# BBB_Headers.net
KiCad netlist of a schematic drawn in Altium Designer
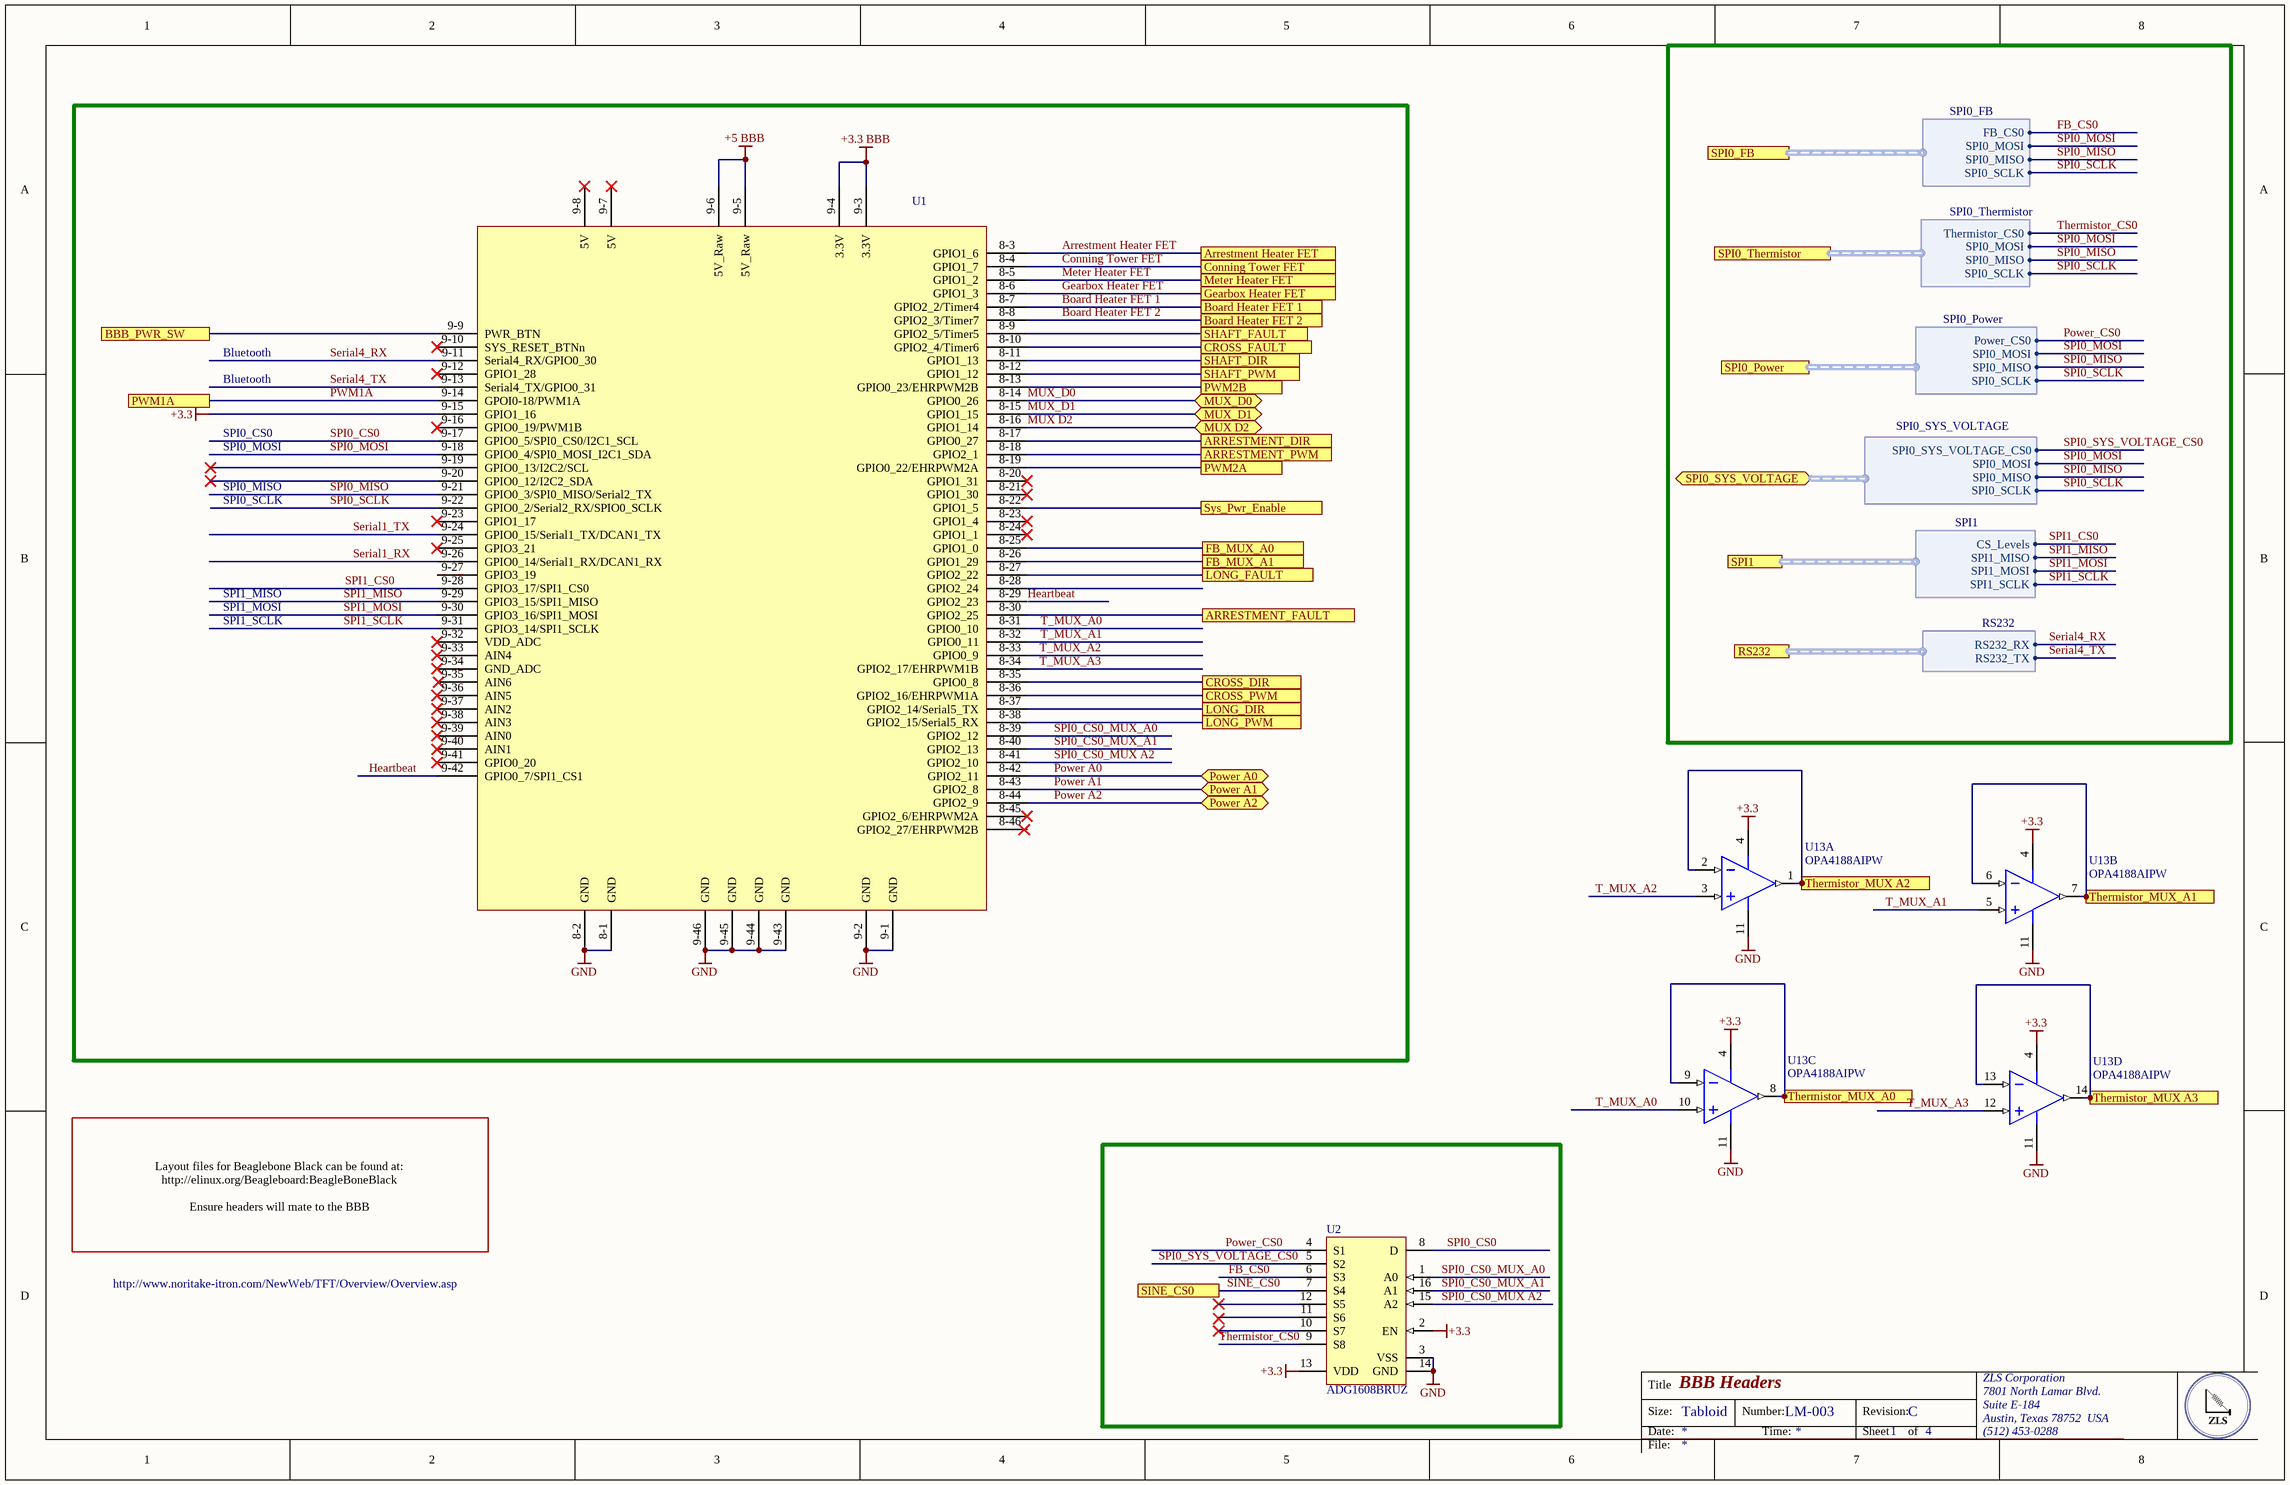
[diagram p0: BBB Headers.SchDoc]

(export (version "E")
  (design (tool "Eeschema 10.0.6"))
  (components
    (comp (ref "U1")
      (value "BBB Header x 2")
      (footprint "Beaglebone Black Thru")
      (description "Beaglebone Black Header")
      (fields
        (field (name "MANUFACTURER") "Samtec Inc.")
        (field (name "MANUFACTURER PART NUMBER") "SSW-123-03-G-D")
      )
      (libsource (lib "ZLS_Schematic_lib") (part "Beaglebone_Black"))
    )
    (comp (ref "U2")
      (value "ADG1608BRUZ")
      (footprint "ADI-RU-16_M")
      (description "4.5 Ohm Ron, 8-Channel +/-5 V,+12 V, +5 V and +3.3 V Multiplexer, 16-pin SOP (RU-16), Tube")
      (fields (field (name "MANUFACTURER") "Analog Devices Inc.") (field (name "BASE PART NUMBER") "ADG1608"))
      (libsource (lib "Altium Content Vault") (part "CMP-0793-00136-1"))
    )
    (comp (ref "U13")
      (value "OPA4188AIPW")
      (footprint "PW0014A_L")
      (fields (field (name "MANUFACTURER") "Texas Instruments"))
      (libsource (lib "Altium Content Vault") (part "TI-OPA4188-PW14"))
    )
  )
  (nets
    (net (code "7") (name "+3.3") (class "Default")
      (node (ref "U1") (pin "9-15") (pinfunction "GPIO1_16_9-15") (pintype "passive"))
      (node (ref "U13") (pin "4") (pinfunction "V+_4") (pintype "power_in"))
      (node (ref "U2") (pin "13") (pinfunction "VDD_13") (pintype "power_in"))
      (node (ref "U2") (pin "2") (pinfunction "EN_2") (pintype "input"))
    )
    (net (code "8") (name "+3.3 BBB") (class "Default")
      (node (ref "U1") (pin "9-3") (pinfunction "3.3V_9-3") (pintype "passive"))
      (node (ref "U1") (pin "9-4") (pinfunction "3.3V_9-4") (pintype "passive"))
    )
    (net (code "9") (name "+5 BBB") (class "Default")
      (node (ref "U1") (pin "9-5") (pinfunction "5V_Raw_9-5") (pintype "passive"))
      (node (ref "U1") (pin "9-6") (pinfunction "5V_Raw_9-6") (pintype "passive"))
    )
    (net (code "10") (name "/ARRESTMENT_DIR") (class "Default")
      (node (ref "U1") (pin "8-17") (pinfunction "GPIO0_27_8-17") (pintype "passive"))
    )
    (net (code "11") (name "/ARRESTMENT_FAULT") (class "Default")
      (node (ref "U1") (pin "8-30") (pinfunction "GPIO2_25_8-30") (pintype "passive"))
    )
    (net (code "12") (name "/ARRESTMENT_PWM") (class "Default")
      (node (ref "U1") (pin "8-18") (pinfunction "GPIO2_1_8-18") (pintype "passive"))
    )
    (net (code "13") (name "/Arrestment Heater FET") (class "Default")
      (node (ref "U1") (pin "8-3") (pinfunction "GPIO1_6_8-3") (pintype "passive"))
    )
    (net (code "14") (name "/BBB_PWR_SW") (class "Default")
      (node (ref "U1") (pin "9-9") (pinfunction "PWR_BTN_9-9") (pintype "passive"))
    )
    (net (code "15") (name "/Board Heater FET 1") (class "Default")
      (node (ref "U1") (pin "8-7") (pinfunction "GPIO2_2/Timer4_8-7") (pintype "passive"))
    )
    (net (code "16") (name "/Board Heater FET 2") (class "Default")
      (node (ref "U1") (pin "8-8") (pinfunction "GPIO2_3/Timer7_8-8") (pintype "passive"))
    )
    (net (code "17") (name "/CROSS_DIR") (class "Default")
      (node (ref "U1") (pin "8-35") (pinfunction "GPIO0_8_8-35") (pintype "passive"))
    )
    (net (code "18") (name "/CROSS_FAULT") (class "Default")
      (node (ref "U1") (pin "8-10") (pinfunction "GPIO2_4/Timer6_8-10") (pintype "passive"))
    )
    (net (code "19") (name "/CROSS_PWM") (class "Default")
      (node (ref "U1") (pin "8-36") (pinfunction "GPIO2_16/EHRPWM1A_8-36") (pintype "passive"))
    )
    (net (code "20") (name "/Conning Tower FET") (class "Default")
      (node (ref "U1") (pin "8-4") (pinfunction "GPIO1_7_8-4") (pintype "passive"))
    )
    (net (code "21") (name "/FB_CS0") (class "Default")
      (node (ref "U2") (pin "6") (pinfunction "S3_6") (pintype "passive"))
    )
    (net (code "22") (name "/FB_MUX_A0") (class "Default")
      (node (ref "U1") (pin "8-25") (pinfunction "GPIO1_0_8-25") (pintype "passive"))
    )
    (net (code "23") (name "/FB_MUX_A1") (class "Default")
      (node (ref "U1") (pin "8-26") (pinfunction "GPIO1_29_8-26") (pintype "passive"))
    )
    (net (code "24") (name "/Gearbox Heater FET") (class "Default")
      (node (ref "U1") (pin "8-6") (pinfunction "GPIO1_3_8-6") (pintype "passive"))
    )
    (net (code "25") (name "/Heartbeat") (class "Default")
      (node (ref "U1") (pin "8-29") (pinfunction "GPIO2_23_8-29") (pintype "passive"))
      (node (ref "U1") (pin "9-42") (pinfunction "GPIO0_7/SPI1_CS1_9-42") (pintype "passive"))
    )
    (net (code "26") (name "/LONG_DIR") (class "Default")
      (node (ref "U1") (pin "8-37") (pinfunction "GPIO2_14/Serial5_TX_8-37") (pintype "passive"))
    )
    (net (code "27") (name "/LONG_FAULT") (class "Default")
      (node (ref "U1") (pin "8-27") (pinfunction "GPIO2_22_8-27") (pintype "passive"))
    )
    (net (code "28") (name "/LONG_PWM") (class "Default")
      (node (ref "U1") (pin "8-38") (pinfunction "GPIO2_15/Serial5_RX_8-38") (pintype "passive"))
    )
    (net (code "29") (name "/MUX D2") (class "Default")
      (node (ref "U1") (pin "8-16") (pinfunction "GPIO1_14_8-16") (pintype "passive"))
    )
    (net (code "30") (name "/MUX_D0") (class "Default")
      (node (ref "U1") (pin "8-14") (pinfunction "GPIO0_26_8-14") (pintype "passive"))
    )
    (net (code "31") (name "/MUX_D1") (class "Default")
      (node (ref "U1") (pin "8-15") (pinfunction "GPIO1_15_8-15") (pintype "passive"))
    )
    (net (code "32") (name "/Meter Heater FET") (class "Default")
      (node (ref "U1") (pin "8-5") (pinfunction "GPIO1_2_8-5") (pintype "passive"))
    )
    (net (code "33") (name "/PWM1A") (class "Default")
      (node (ref "U1") (pin "9-14") (pinfunction "GPOI0-18/PWM1A_9-14") (pintype "passive"))
    )
    (net (code "34") (name "/PWM2A") (class "Default")
      (node (ref "U1") (pin "8-19") (pinfunction "GPIO0_22/EHRPWM2A_8-19") (pintype "passive"))
    )
    (net (code "35") (name "/PWM2B") (class "Default")
      (node (ref "U1") (pin "8-13") (pinfunction "GPIO0_23/EHRPWM2B_8-13") (pintype "passive"))
    )
    (net (code "36") (name "/Power A0") (class "Default")
      (node (ref "U1") (pin "8-42") (pinfunction "GPIO2_11_8-42") (pintype "passive"))
    )
    (net (code "37") (name "/Power A1") (class "Default")
      (node (ref "U1") (pin "8-43") (pinfunction "GPIO2_8_8-43") (pintype "passive"))
    )
    (net (code "38") (name "/Power A2") (class "Default")
      (node (ref "U1") (pin "8-44") (pinfunction "GPIO2_9_8-44") (pintype "passive"))
    )
    (net (code "39") (name "/Power_CS0") (class "Default")
      (node (ref "U2") (pin "4") (pinfunction "S1_4") (pintype "passive"))
    )
    (net (code "40") (name "/SHAFT_DIR") (class "Default")
      (node (ref "U1") (pin "8-11") (pinfunction "GPIO1_13_8-11") (pintype "passive"))
    )
    (net (code "41") (name "/SHAFT_FAULT") (class "Default")
      (node (ref "U1") (pin "8-9") (pinfunction "GPIO2_5/Timer5_8-9") (pintype "passive"))
    )
    (net (code "42") (name "/SHAFT_PWM") (class "Default")
      (node (ref "U1") (pin "8-12") (pinfunction "GPIO1_12_8-12") (pintype "passive"))
    )
    (net (code "43") (name "/SINE_CS0") (class "Default")
      (node (ref "U2") (pin "7") (pinfunction "S4_7") (pintype "passive"))
    )
    (net (code "44") (name "/SPI0_CS0") (class "Default")
      (node (ref "U1") (pin "9-17") (pinfunction "GPIO0_5/SPI0_CS0/I2C1_SCL_9-17") (pintype "passive"))
      (node (ref "U2") (pin "8") (pinfunction "D_8") (pintype "passive"))
    )
    (net (code "45") (name "/SPI0_CS0_MUX A2") (class "Default")
      (node (ref "U1") (pin "8-41") (pinfunction "GPIO2_10_8-41") (pintype "passive"))
      (node (ref "U2") (pin "15") (pinfunction "A2_15") (pintype "input"))
    )
    (net (code "46") (name "/SPI0_CS0_MUX_A0") (class "Default")
      (node (ref "U1") (pin "8-39") (pinfunction "GPIO2_12_8-39") (pintype "passive"))
      (node (ref "U2") (pin "1") (pinfunction "A0_1") (pintype "input"))
    )
    (net (code "47") (name "/SPI0_CS0_MUX_A1") (class "Default")
      (node (ref "U1") (pin "8-40") (pinfunction "GPIO2_13_8-40") (pintype "passive"))
      (node (ref "U2") (pin "16") (pinfunction "A1_16") (pintype "input"))
    )
    (net (code "48") (name "/SPI0_MISO") (class "Default")
      (node (ref "U1") (pin "9-21") (pinfunction "GPIO0_3/SPI0_MISO/Serial2_TX_9-21") (pintype "passive"))
    )
    (net (code "49") (name "/SPI0_MOSI") (class "Default")
      (node (ref "U1") (pin "9-18") (pinfunction "GPIO0_4/SPI0_MOSI_I2C1_SDA_9-18") (pintype "passive"))
    )
    (net (code "50") (name "/SPI0_SCLK") (class "Default")
      (node (ref "U1") (pin "9-22") (pinfunction "GPIO0_2/Serial2_RX/SPIO0_SCLK_9-22") (pintype "passive"))
    )
    (net (code "51") (name "/SPI0_SYS_VOLTAGE_CS0") (class "Default")
      (node (ref "U2") (pin "5") (pinfunction "S2_5") (pintype "passive"))
    )
    (net (code "52") (name "/SPI1_CS0") (class "Default")
      (node (ref "U1") (pin "9-28") (pinfunction "GPIO3_17/SPI1_CS0_9-28") (pintype "passive"))
    )
    (net (code "53") (name "/SPI1_MISO") (class "Default")
      (node (ref "U1") (pin "9-29") (pinfunction "GPIO3_15/SPI1_MISO_9-29") (pintype "passive"))
    )
    (net (code "54") (name "/SPI1_MOSI") (class "Default")
      (node (ref "U1") (pin "9-30") (pinfunction "GPIO3_16/SPI1_MOSI_9-30") (pintype "passive"))
    )
    (net (code "55") (name "/SPI1_SCLK") (class "Default")
      (node (ref "U1") (pin "9-31") (pinfunction "GPIO3_14/SPI1_SCLK_9-31") (pintype "passive"))
    )
    (net (code "56") (name "/Serial1_RX") (class "Default")
      (node (ref "U1") (pin "9-26") (pinfunction "GPIO0_14/Serial1_RX/DCAN1_RX_9-26") (pintype "passive"))
    )
    (net (code "57") (name "/Serial1_TX") (class "Default")
      (node (ref "U1") (pin "9-24") (pinfunction "GPIO0_15/Serial1_TX/DCAN1_TX_9-24") (pintype "passive"))
    )
    (net (code "58") (name "/Serial4_RX") (class "Default")
      (node (ref "U1") (pin "9-11") (pinfunction "Serial4_RX/GPIO0_30_9-11") (pintype "passive"))
    )
    (net (code "59") (name "/Serial4_TX") (class "Default")
      (node (ref "U1") (pin "9-13") (pinfunction "Serial4_TX/GPIO0_31_9-13") (pintype "passive"))
    )
    (net (code "60") (name "/Sys_Pwr_Enable") (class "Default")
      (node (ref "U1") (pin "8-22") (pinfunction "GPIO1_5_8-22") (pintype "passive"))
    )
    (net (code "61") (name "/T_MUX_A0") (class "Default")
      (node (ref "U1") (pin "8-31") (pinfunction "GPIO0_10_8-31") (pintype "passive"))
      (node (ref "U13") (pin "10") (pinfunction "IN_C+_10") (pintype "input"))
    )
    (net (code "62") (name "/T_MUX_A1") (class "Default")
      (node (ref "U1") (pin "8-32") (pinfunction "GPIO0_11_8-32") (pintype "passive"))
      (node (ref "U13") (pin "5") (pinfunction "IN_B+_5") (pintype "input"))
    )
    (net (code "63") (name "/T_MUX_A2") (class "Default")
      (node (ref "U1") (pin "8-33") (pinfunction "GPIO0_9_8-33") (pintype "passive"))
      (node (ref "U13") (pin "3") (pinfunction "IN_A+_3") (pintype "input"))
    )
    (net (code "64") (name "/T_MUX_A3") (class "Default")
      (node (ref "U1") (pin "8-34") (pinfunction "GPIO2_17/EHRPWM1B_8-34") (pintype "passive"))
      (node (ref "U13") (pin "12") (pinfunction "IN_D+_12") (pintype "input"))
    )
    (net (code "65") (name "/Thermistor_CS0") (class "Default")
      (node (ref "U2") (pin "9") (pinfunction "S8_9") (pintype "passive"))
    )
    (net (code "66") (name "/Thermistor_MUX A2") (class "Default")
      (node (ref "U13") (pin "1") (pinfunction "OUT_A_1") (pintype "output"))
      (node (ref "U13") (pin "2") (pinfunction "IN_A-_2") (pintype "input"))
    )
    (net (code "67") (name "/Thermistor_MUX A3") (class "Default")
      (node (ref "U13") (pin "13") (pinfunction "IN_D-_13") (pintype "input"))
      (node (ref "U13") (pin "14") (pinfunction "OUT_D_14") (pintype "output"))
    )
    (net (code "68") (name "/Thermistor_MUX_A0") (class "Default")
      (node (ref "U13") (pin "8") (pinfunction "OUT_C_8") (pintype "output"))
      (node (ref "U13") (pin "9") (pinfunction "IN_C-_9") (pintype "input"))
    )
    (net (code "69") (name "/Thermistor_MUX_A1") (class "Default")
      (node (ref "U13") (pin "6") (pinfunction "IN_B-_6") (pintype "input"))
      (node (ref "U13") (pin "7") (pinfunction "OUT_B_7") (pintype "output"))
    )
    (net (code "76") (name "GND") (class "Default")
      (node (ref "U1") (pin "8-1") (pinfunction "GND_8-1") (pintype "passive"))
      (node (ref "U1") (pin "8-2") (pinfunction "GND_8-2") (pintype "passive"))
      (node (ref "U1") (pin "9-1") (pinfunction "GND_9-1") (pintype "passive"))
      (node (ref "U1") (pin "9-2") (pinfunction "GND_9-2") (pintype "passive"))
      (node (ref "U1") (pin "9-43") (pinfunction "GND_9-43") (pintype "passive"))
      (node (ref "U1") (pin "9-44") (pinfunction "GND_9-44") (pintype "passive"))
      (node (ref "U1") (pin "9-45") (pinfunction "GND_9-45") (pintype "passive"))
      (node (ref "U1") (pin "9-46") (pinfunction "GND_9-46") (pintype "passive"))
      (node (ref "U13") (pin "11") (pinfunction "V-_11") (pintype "power_in"))
      (node (ref "U2") (pin "14") (pinfunction "GND_14") (pintype "power_in"))
      (node (ref "U2") (pin "3") (pinfunction "VSS_3") (pintype "power_in"))
    )
    (net (code "77") (name "unconnected-(U1-5V-Pad9-7)") (class "Default")
      (node (ref "U1") (pin "9-7") (pinfunction "5V_9-7") (pintype "passive+no_connect"))
    )
    (net (code "78") (name "unconnected-(U1-5V-Pad9-8)") (class "Default")
      (node (ref "U1") (pin "9-8") (pinfunction "5V_9-8") (pintype "passive+no_connect"))
    )
    (net (code "79") (name "unconnected-(U1-AIN0-Pad9-39)") (class "Default")
      (node (ref "U1") (pin "9-39") (pinfunction "AIN0_9-39") (pintype "passive+no_connect"))
    )
    (net (code "80") (name "unconnected-(U1-AIN1-Pad9-40)") (class "Default")
      (node (ref "U1") (pin "9-40") (pinfunction "AIN1_9-40") (pintype "passive+no_connect"))
    )
    (net (code "81") (name "unconnected-(U1-AIN2-Pad9-37)") (class "Default")
      (node (ref "U1") (pin "9-37") (pinfunction "AIN2_9-37") (pintype "passive+no_connect"))
    )
    (net (code "82") (name "unconnected-(U1-AIN3-Pad9-38)") (class "Default")
      (node (ref "U1") (pin "9-38") (pinfunction "AIN3_9-38") (pintype "passive+no_connect"))
    )
    (net (code "83") (name "unconnected-(U1-AIN4-Pad9-33)") (class "Default")
      (node (ref "U1") (pin "9-33") (pinfunction "AIN4_9-33") (pintype "passive+no_connect"))
    )
    (net (code "84") (name "unconnected-(U1-AIN5-Pad9-36)") (class "Default")
      (node (ref "U1") (pin "9-36") (pinfunction "AIN5_9-36") (pintype "passive+no_connect"))
    )
    (net (code "85") (name "unconnected-(U1-AIN6-Pad9-35)") (class "Default")
      (node (ref "U1") (pin "9-35") (pinfunction "AIN6_9-35") (pintype "passive"))
    )
    (net (code "86") (name "unconnected-(U1-GND_ADC-Pad9-34)") (class "Default")
      (node (ref "U1") (pin "9-34") (pinfunction "GND_ADC_9-34") (pintype "passive+no_connect"))
    )
    (net (code "87") (name "unconnected-(U1-GPIO0_12{slash}I2C2_SDA-Pad9-20)") (class "Default")
      (node (ref "U1") (pin "9-20") (pinfunction "GPIO0_12/I2C2_SDA_9-20") (pintype "passive+no_connect"))
    )
    (net (code "88") (name "unconnected-(U1-GPIO0_13{slash}I2C2{slash}SCL-Pad9-19)") (class "Default")
      (node (ref "U1") (pin "9-19") (pinfunction "GPIO0_13/I2C2/SCL_9-19") (pintype "passive+no_connect"))
    )
    (net (code "89") (name "unconnected-(U1-GPIO0_19{slash}PWM1B-Pad9-16)") (class "Default")
      (node (ref "U1") (pin "9-16") (pinfunction "GPIO0_19/PWM1B_9-16") (pintype "passive+no_connect"))
    )
    (net (code "90") (name "unconnected-(U1-GPIO0_20-Pad9-41)") (class "Default")
      (node (ref "U1") (pin "9-41") (pinfunction "GPIO0_20_9-41") (pintype "passive+no_connect"))
    )
    (net (code "91") (name "unconnected-(U1-GPIO1_1-Pad8-24)") (class "Default")
      (node (ref "U1") (pin "8-24") (pinfunction "GPIO1_1_8-24") (pintype "passive+no_connect"))
    )
    (net (code "92") (name "unconnected-(U1-GPIO1_4-Pad8-23)") (class "Default")
      (node (ref "U1") (pin "8-23") (pinfunction "GPIO1_4_8-23") (pintype "passive+no_connect"))
    )
    (net (code "93") (name "unconnected-(U1-GPIO1_17-Pad9-23)") (class "Default")
      (node (ref "U1") (pin "9-23") (pinfunction "GPIO1_17_9-23") (pintype "passive+no_connect"))
    )
    (net (code "94") (name "unconnected-(U1-GPIO1_28-Pad9-12)") (class "Default")
      (node (ref "U1") (pin "9-12") (pinfunction "GPIO1_28_9-12") (pintype "passive+no_connect"))
    )
    (net (code "95") (name "unconnected-(U1-GPIO1_30-Pad8-21)") (class "Default")
      (node (ref "U1") (pin "8-21") (pinfunction "GPIO1_30_8-21") (pintype "passive+no_connect"))
    )
    (net (code "96") (name "unconnected-(U1-GPIO1_31-Pad8-20)") (class "Default")
      (node (ref "U1") (pin "8-20") (pinfunction "GPIO1_31_8-20") (pintype "passive+no_connect"))
    )
    (net (code "97") (name "unconnected-(U1-GPIO2_6{slash}EHRPWM2A-Pad8-45)") (class "Default")
      (node (ref "U1") (pin "8-45") (pinfunction "GPIO2_6/EHRPWM2A_8-45") (pintype "passive+no_connect"))
    )
    (net (code "98") (name "unconnected-(U1-GPIO2_24-Pad8-28)") (class "Default")
      (node (ref "U1") (pin "8-28") (pinfunction "GPIO2_24_8-28") (pintype "passive"))
    )
    (net (code "99") (name "unconnected-(U1-GPIO2_27{slash}EHRPWM2B-Pad8-46)") (class "Default")
      (node (ref "U1") (pin "8-46") (pinfunction "GPIO2_27/EHRPWM2B_8-46") (pintype "passive"))
    )
    (net (code "100") (name "unconnected-(U1-GPIO3_19-Pad9-27)") (class "Default")
      (node (ref "U1") (pin "9-27") (pinfunction "GPIO3_19_9-27") (pintype "passive"))
    )
    (net (code "101") (name "unconnected-(U1-GPIO3_21-Pad9-25)") (class "Default")
      (node (ref "U1") (pin "9-25") (pinfunction "GPIO3_21_9-25") (pintype "passive+no_connect"))
    )
    (net (code "102") (name "unconnected-(U1-SYS_RESET_BTNn-Pad9-10)") (class "Default")
      (node (ref "U1") (pin "9-10") (pinfunction "SYS_RESET_BTNn_9-10") (pintype "passive+no_connect"))
    )
    (net (code "103") (name "unconnected-(U1-VDD_ADC-Pad9-32)") (class "Default")
      (node (ref "U1") (pin "9-32") (pinfunction "VDD_ADC_9-32") (pintype "passive+no_connect"))
    )
    (net (code "104") (name "unconnected-(U2-S5-Pad12)") (class "Default")
      (node (ref "U2") (pin "12") (pinfunction "S5_12") (pintype "passive+no_connect"))
    )
    (net (code "105") (name "unconnected-(U2-S6-Pad11)") (class "Default")
      (node (ref "U2") (pin "11") (pinfunction "S6_11") (pintype "passive"))
    )
    (net (code "106") (name "unconnected-(U2-S7-Pad10)") (class "Default")
      (node (ref "U2") (pin "10") (pinfunction "S7_10") (pintype "passive+no_connect"))
    )
  )
)
